# ST25DV.net
KiCad netlist of a schematic drawn in Altium Designer
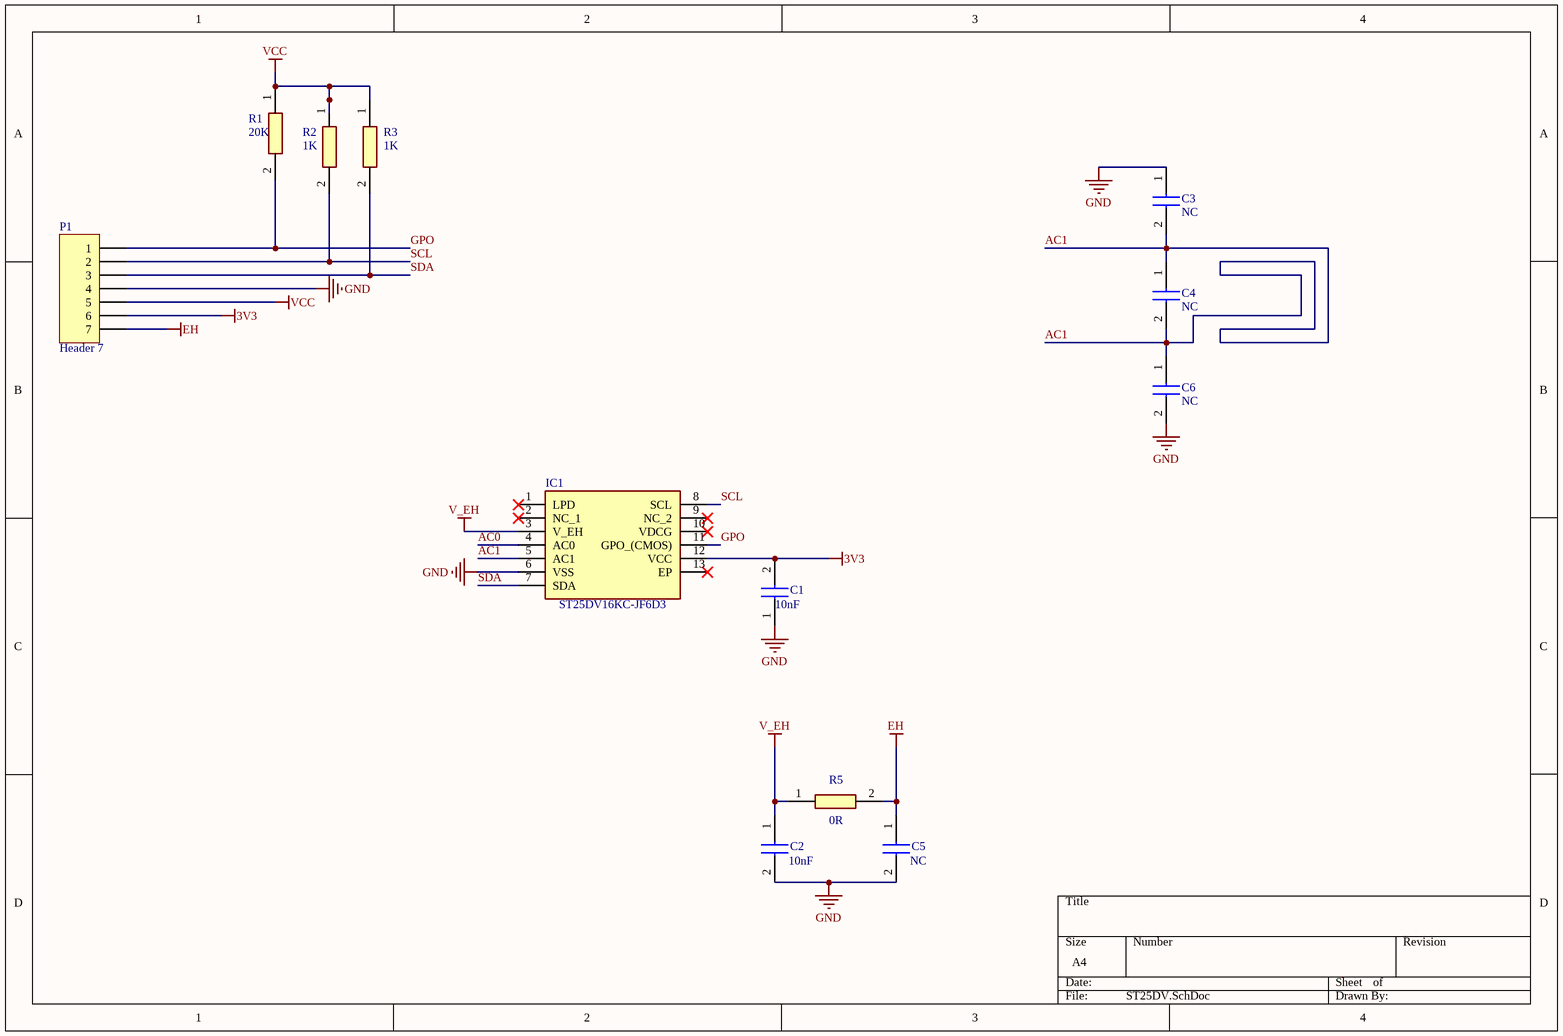
[diagram p0: ST25DV.SchDoc]

(export (version "E")
  (design (tool "Eeschema 10.0.6"))
  (components
    (comp (ref "C1")
      (value "10nF")
      (footprint "Test_Library:CAPC1005X60N")
      (description "Capacitor")
      (fields
        (field (name "MANUFACTURER_PART_NUMBER") "VJ0402Y103KXAAC")
        (field (name "MOUSER PART NUMBER") "77-VJ0402Y103KXAAC")
      )
      (libsource (lib "*") (part "VJ0402Y103KXAAC"))
    )
    (comp (ref "C2")
      (value "10nF")
      (footprint "Test_Library:CAPC1005X60N")
      (description "Capacitor")
      (fields
        (field (name "MANUFACTURER_PART_NUMBER") "VJ0402Y103KXAAC")
        (field (name "MOUSER PART NUMBER") "77-VJ0402Y103KXAAC")
      )
      (libsource (lib "*") (part "VJ0402Y103KXAAC"))
    )
    (comp (ref "C3")
      (value "NC")
      (footprint "Test_Library:CAPC1005X60N")
      (description "Capacitor")
      (fields
        (field (name "MANUFACTURER_PART_NUMBER") "VJ0402Y103KXAAC")
        (field (name "MOUSER PART NUMBER") "77-VJ0402Y103KXAAC")
      )
      (libsource (lib "*") (part "VJ0402Y103KXAAC"))
    )
    (comp (ref "C4")
      (value "NC")
      (footprint "Test_Library:CAPC1005X60N")
      (description "Capacitor")
      (fields
        (field (name "MANUFACTURER_PART_NUMBER") "VJ0402Y103KXAAC")
        (field (name "MOUSER PART NUMBER") "77-VJ0402Y103KXAAC")
      )
      (libsource (lib "*") (part "VJ0402Y103KXAAC"))
    )
    (comp (ref "C5")
      (value "NC")
      (footprint "Test_Library:CAPC1005X60N")
      (description "Capacitor")
      (fields
        (field (name "MANUFACTURER_PART_NUMBER") "VJ0402Y103KXAAC")
        (field (name "MOUSER PART NUMBER") "77-VJ0402Y103KXAAC")
      )
      (libsource (lib "*") (part "VJ0402Y103KXAAC"))
    )
    (comp (ref "C6")
      (value "NC")
      (footprint "Test_Library:CAPC1005X60N")
      (description "Capacitor")
      (fields
        (field (name "MANUFACTURER_PART_NUMBER") "VJ0402Y103KXAAC")
        (field (name "MOUSER PART NUMBER") "77-VJ0402Y103KXAAC")
      )
      (libsource (lib "*") (part "VJ0402Y103KXAAC"))
    )
    (comp (ref "IC1")
      (value "ST25DV16KC-JF6D3")
      (footprint "Test_Library:ST25DV64KCJF6D3")
      (description "Integrated Circuit")
      (fields (field (name "MOUSER PART NUMBER") "511-ST25DV16KC-JF6D3"))
      (libsource (lib "*") (part "ST25DV16KC-JF6D3"))
    )
    (comp (ref "P1")
      (value "Header 7")
      (footprint "HDR1X7")
      (description "Header, 7-Pin")
      (fields (field (name "PUBLISHER") "Altium Limited"))
      (libsource (lib "Miscellaneous Connectors") (part "Header 7"))
    )
    (comp (ref "R1")
      (value "20K")
      (footprint "Test_Library:CRCW0402200KFKED")
      (description "Resistor")
      (fields (field (name "MANUFACTURER_PART_NUMBER") "CRCW04021K65FKEE"))
      (libsource (lib "*") (part "CRCW04021K65FKEE"))
    )
    (comp (ref "R2")
      (value "1K")
      (footprint "Test_Library:CRCW0402200KFKED")
      (description "Resistor")
      (fields (field (name "MANUFACTURER_PART_NUMBER") "CRCW04021K65FKEE"))
      (libsource (lib "*") (part "CRCW04021K65FKEE"))
    )
    (comp (ref "R3")
      (value "1K")
      (footprint "Test_Library:CRCW0402200KFKED")
      (description "Resistor")
      (fields (field (name "MANUFACTURER_PART_NUMBER") "CRCW04021K65FKEE"))
      (libsource (lib "*") (part "CRCW04021K65FKEE"))
    )
    (comp (ref "R5")
      (value "0R")
      (footprint "Test_Library:CRCW0402200KFKED")
      (description "Resistor")
      (fields (field (name "MANUFACTURER_PART_NUMBER") "CRCW04021K65FKEE"))
      (libsource (lib "") (part "CRCW04021K65FKEE_1"))
    )
  )
  (nets
    (net (code "1") (name "/AC0") (class "Default")
      (node (ref "IC1") (pin "4") (pinfunction "AC0_4") (pintype "passive"))
    )
    (net (code "2") (name "/AC1") (class "Default")
      (node (ref "C3") (pin "2") (pinfunction "2_2") (pintype "passive"))
      (node (ref "C4") (pin "1") (pinfunction "1_1") (pintype "passive"))
      (node (ref "C4") (pin "2") (pinfunction "2_2") (pintype "passive"))
      (node (ref "C6") (pin "1") (pinfunction "1_1") (pintype "passive"))
      (node (ref "IC1") (pin "5") (pinfunction "AC1_5") (pintype "passive"))
    )
    (net (code "3") (name "/GPO") (class "Default")
      (node (ref "IC1") (pin "11") (pinfunction "GPO_(CMOS)_11") (pintype "passive"))
      (node (ref "P1") (pin "1") (pinfunction "1_1") (pintype "passive"))
      (node (ref "R1") (pin "2") (pinfunction "2_2") (pintype "passive"))
    )
    (net (code "4") (name "/SCL") (class "Default")
      (node (ref "IC1") (pin "8") (pinfunction "SCL_8") (pintype "passive"))
      (node (ref "P1") (pin "2") (pinfunction "2_2") (pintype "passive"))
      (node (ref "R2") (pin "2") (pinfunction "2_2") (pintype "passive"))
    )
    (net (code "5") (name "/SDA") (class "Default")
      (node (ref "IC1") (pin "7") (pinfunction "SDA_7") (pintype "passive"))
      (node (ref "P1") (pin "3") (pinfunction "3_3") (pintype "passive"))
      (node (ref "R3") (pin "2") (pinfunction "2_2") (pintype "passive"))
    )
    (net (code "6") (name "3V3") (class "Default")
      (node (ref "C1") (pin "2") (pinfunction "2_2") (pintype "passive"))
      (node (ref "IC1") (pin "12") (pinfunction "VCC_12") (pintype "passive"))
      (node (ref "P1") (pin "6") (pinfunction "6_6") (pintype "passive"))
    )
    (net (code "7") (name "EH") (class "Default")
      (node (ref "C5") (pin "1") (pinfunction "1_1") (pintype "passive"))
      (node (ref "P1") (pin "7") (pinfunction "7_7") (pintype "passive"))
      (node (ref "R5") (pin "2") (pinfunction "2_2") (pintype "passive"))
    )
    (net (code "8") (name "GND") (class "Default")
      (node (ref "C1") (pin "1") (pinfunction "1_1") (pintype "passive"))
      (node (ref "C2") (pin "2") (pinfunction "2_2") (pintype "passive"))
      (node (ref "C3") (pin "1") (pinfunction "1_1") (pintype "passive"))
      (node (ref "C5") (pin "2") (pinfunction "2_2") (pintype "passive"))
      (node (ref "C6") (pin "2") (pinfunction "2_2") (pintype "passive"))
      (node (ref "IC1") (pin "6") (pinfunction "VSS_6") (pintype "passive"))
      (node (ref "P1") (pin "4") (pinfunction "4_4") (pintype "passive"))
    )
    (net (code "9") (name "VCC") (class "Default")
      (node (ref "P1") (pin "5") (pinfunction "5_5") (pintype "passive"))
      (node (ref "R1") (pin "1") (pinfunction "1_1") (pintype "passive"))
      (node (ref "R2") (pin "1") (pinfunction "1_1") (pintype "passive"))
      (node (ref "R3") (pin "1") (pinfunction "1_1") (pintype "passive"))
    )
    (net (code "10") (name "V_EH") (class "Default")
      (node (ref "C2") (pin "1") (pinfunction "1_1") (pintype "passive"))
      (node (ref "IC1") (pin "3") (pinfunction "V_EH_3") (pintype "passive"))
      (node (ref "R5") (pin "1") (pinfunction "1_1") (pintype "passive"))
    )
    (net (code "11") (name "unconnected-(IC1-EP-Pad13)") (class "Default")
      (node (ref "IC1") (pin "13") (pinfunction "EP_13") (pintype "passive+no_connect"))
    )
    (net (code "12") (name "unconnected-(IC1-LPD-Pad1)") (class "Default")
      (node (ref "IC1") (pin "1") (pinfunction "LPD_1") (pintype "passive+no_connect"))
    )
    (net (code "13") (name "unconnected-(IC1-NC_1-Pad2)") (class "Default")
      (node (ref "IC1") (pin "2") (pinfunction "NC_1_2") (pintype "passive+no_connect"))
    )
    (net (code "14") (name "unconnected-(IC1-NC_2-Pad9)") (class "Default")
      (node (ref "IC1") (pin "9") (pinfunction "NC_2_9") (pintype "passive+no_connect"))
    )
    (net (code "15") (name "unconnected-(IC1-VDCG-Pad10)") (class "Default")
      (node (ref "IC1") (pin "10") (pinfunction "VDCG_10") (pintype "passive+no_connect"))
    )
  )
)
